# ToneDroneOsc.net
KiCad netlist of a schematic drawn in Altium Designer
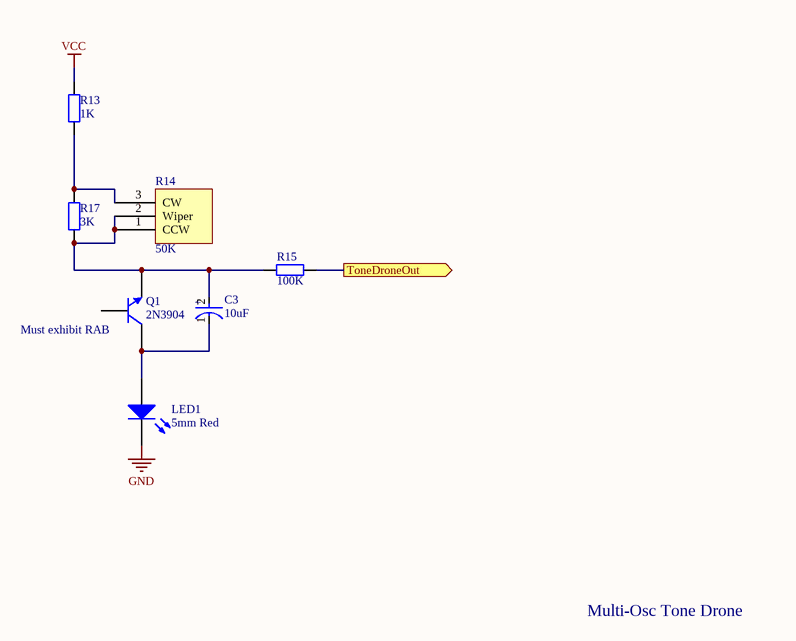
[diagram p0: ToneDroneOsc.SchDoc]

(export (version "E")
  (design (tool "Eeschema 10.0.6"))
  (components
    (comp (ref "C3")
      (value "10uF")
      (footprint "FP-ESLE3-MFG")
      (description "CAP ALUM 10UF 20% 100V THRU HOLE")
      (fields (field (name "TOLERANCE") "20%") (field (name "MANUFACTURER PART NUMBER") "ESL106M100AE3AA"))
      (libsource (lib "Altium Content Vault") (part "cf48714ba7e38822c1575c7ec0b6d1f"))
    )
    (comp (ref "LED1")
      (value "5mm Red")
      (footprint "Type 5mm")
      (description "THT LED round mono-color color lens, WL-TMRW, Red")
      (fields (field (name "PARTNUMBER") "151051RS11000") (field (name "MANUFACTURER") "Wuerth Elektronik"))
      (libsource (lib "Altium Content Vault") (part "WE-LED_K1A2-2"))
    )
    (comp (ref "Q1")
      (value "2N3904")
      (footprint "TO-92A")
      (description "NPN General Purpose Amplifier")
      (fields (field (name "PUBLISHER") "Altium Limited"))
      (libsource (lib "Miscellaneous Devices") (part "2N3904"))
    )
    (comp (ref "R13")
      (value "1K")
      (footprint "AXIAL-0.4")
      (description "Resistor")
      (fields (field (name "PUBLISHER") "Altium Limited"))
      (libsource (lib "Miscellaneous Devices") (part "Res2"))
    )
    (comp (ref "R14") (value "50K") (footprint "TrimmerPot") (libsource (lib "Schlib") (part "TrimmerPot")))
    (comp (ref "R15")
      (value "100K")
      (footprint "AXIAL-0.4")
      (description "Resistor")
      (fields (field (name "PUBLISHER") "Altium Limited"))
      (libsource (lib "") (part "Res2_1"))
    )
    (comp (ref "R17")
      (value "3K")
      (footprint "AXIAL-0.4")
      (description "Resistor")
      (fields (field (name "PUBLISHER") "Altium Limited"))
      (libsource (lib "Miscellaneous Devices") (part "Res2"))
    )
  )
  (nets
    (net (code "1") (name "/ToneDroneOut") (class "Default")
      (node (ref "R15") (pin "1") (pinfunction "1_1") (pintype "passive"))
    )
    (net (code "2") (name "GND") (class "Default")
      (node (ref "LED1") (pin "1") (pinfunction "K_1") (pintype "passive"))
    )
    (net (code "3") (name "Net-(C3-A)") (class "Default")
      (node (ref "C3") (pin "2") (pinfunction "A_2") (pintype "passive"))
      (node (ref "Q1") (pin "1") (pinfunction "E_1") (pintype "passive"))
      (node (ref "R14") (pin "1") (pinfunction "CCW_1") (pintype "passive"))
      (node (ref "R14") (pin "2") (pinfunction "Wiper_2") (pintype "passive"))
      (node (ref "R15") (pin "2") (pinfunction "2_2") (pintype "passive"))
      (node (ref "R17") (pin "1") (pinfunction "1_1") (pintype "passive"))
    )
    (net (code "4") (name "Net-(C3-C)") (class "Default")
      (node (ref "C3") (pin "1") (pinfunction "C_1") (pintype "passive"))
      (node (ref "LED1") (pin "2") (pinfunction "A_2") (pintype "passive"))
      (node (ref "Q1") (pin "3") (pinfunction "C_3") (pintype "passive"))
    )
    (net (code "5") (name "Net-(R14-CW)") (class "Default")
      (node (ref "R13") (pin "1") (pinfunction "1_1") (pintype "passive"))
      (node (ref "R14") (pin "3") (pinfunction "CW_3") (pintype "passive"))
      (node (ref "R17") (pin "2") (pinfunction "2_2") (pintype "passive"))
    )
    (net (code "6") (name "VCC") (class "Default")
      (node (ref "R13") (pin "2") (pinfunction "2_2") (pintype "passive"))
    )
    (net (code "7") (name "unconnected-(Q1-B-Pad2)") (class "Default")
      (node (ref "Q1") (pin "2") (pinfunction "B_2") (pintype "passive"))
    )
  )
)
